# Power_Drive.net
KiCad netlist of a schematic drawn in Altium Designer
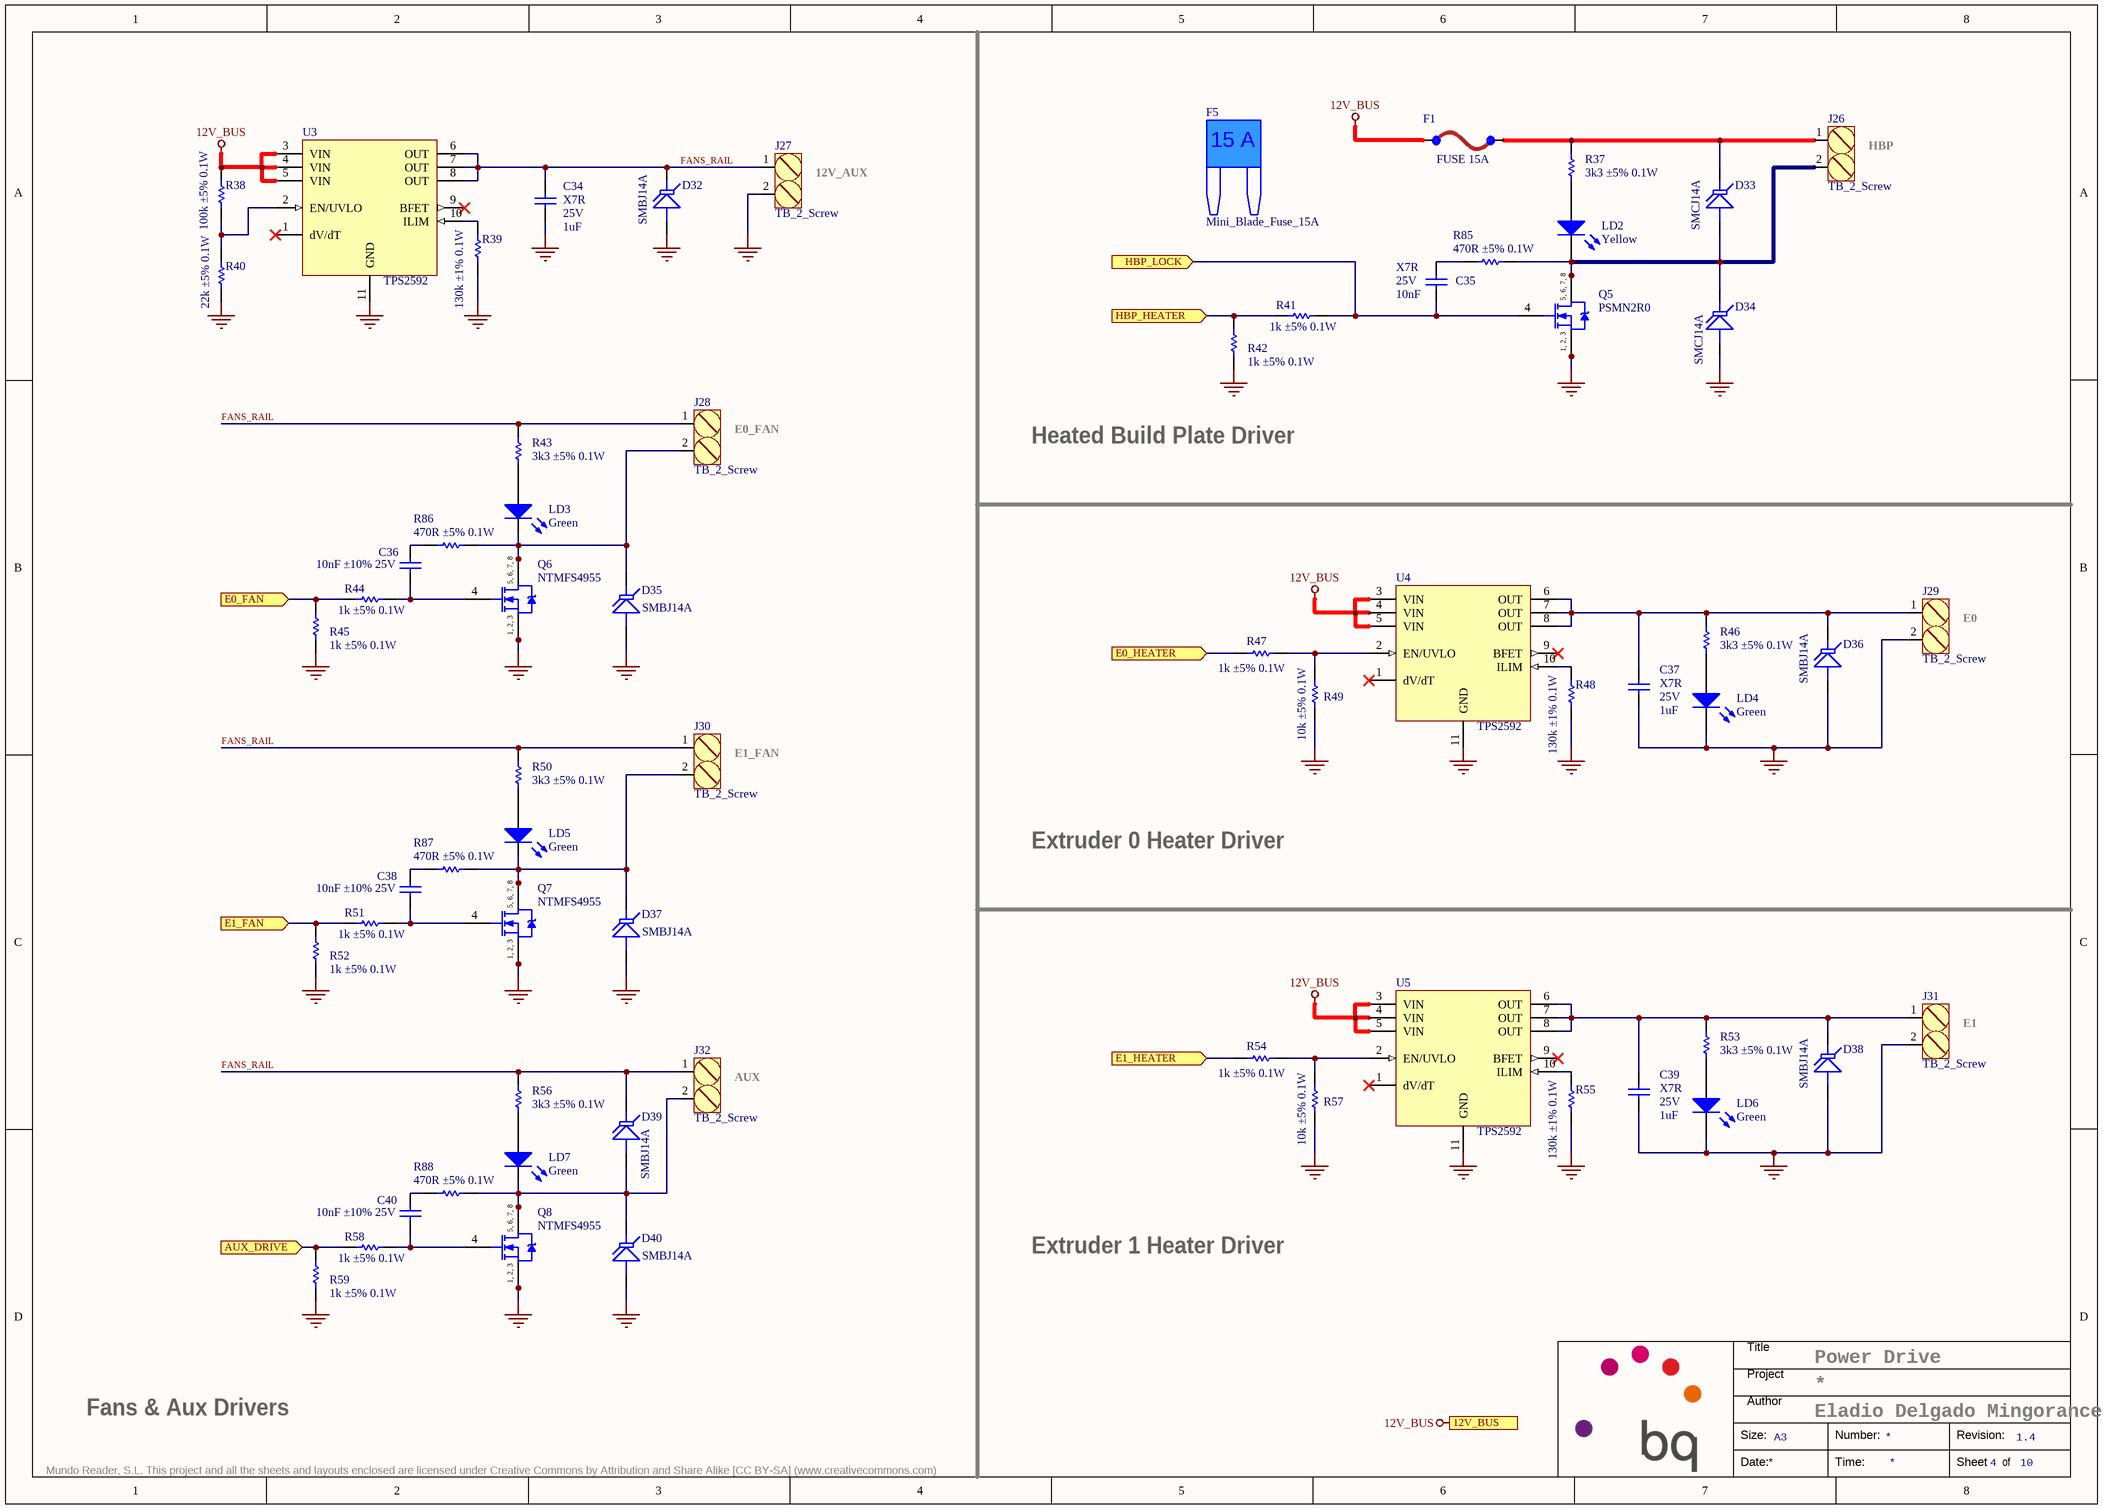
[diagram p0: Power_Drive.SchDoc]

(export (version "E")
  (design (tool "Eeschema 10.0.6"))
  (components
    (comp (ref "C34")
      (value "Capacitor")
      (footprint "C0805")
      (fields
        (field (name "DIELECTRIC") "X7R")
        (field (name "VOLTAGE") "25V")
        (field (name "CAPACITANCE") "1uF")
        (field (name "PART NUMBER") "C0805_1uF_25V_X7R")
        (field (name "TOLERANCE") "±10%")
        (field (name "MANUFACTURER") "TDK")
      )
      (libsource (lib "Pasives_Capacitor_SMD") (part "Capacitor"))
    )
    (comp (ref "C35")
      (value "Capacitor")
      (footprint "C0603")
      (fields
        (field (name "DIELECTRIC") "X7R")
        (field (name "VOLTAGE") "25V")
        (field (name "CAPACITANCE") "10nF")
        (field (name "PART NUMBER") "C0603_10nF_25V_±10%")
        (field (name "TOLERANCE") "±10%")
        (field (name "MANUFACTURER") "Kemet")
      )
      (libsource (lib "Pasives_Capacitor_SMD") (part "Capacitor"))
    )
    (comp (ref "C36")
      (value "10nF ±10% 25V")
      (footprint "C0603")
      (description "Capacitor")
      (fields (field (name "VOLTAGE") "25V") (field (name "PART NUMBER") "C0603_10nF_25V_±10%"))
      (libsource (lib "Pasives_Capacitor_SMD") (part "Capacitor"))
    )
    (comp (ref "C37")
      (value "Capacitor")
      (footprint "C0805")
      (fields
        (field (name "DIELECTRIC") "X7R")
        (field (name "VOLTAGE") "25V")
        (field (name "CAPACITANCE") "1uF")
        (field (name "PART NUMBER") "C0805_1uF_25V_X7R")
        (field (name "TOLERANCE") "±10%")
        (field (name "MANUFACTURER") "TDK")
      )
      (libsource (lib "Pasives_Capacitor_SMD") (part "Capacitor"))
    )
    (comp (ref "C38")
      (value "10nF ±10% 25V")
      (footprint "C0603")
      (description "Capacitor")
      (fields (field (name "VOLTAGE") "25V") (field (name "PART NUMBER") "C0603_10nF_25V_±10%"))
      (libsource (lib "Pasives_Capacitor_SMD") (part "Capacitor"))
    )
    (comp (ref "C39")
      (value "Capacitor")
      (footprint "C0805")
      (fields
        (field (name "DIELECTRIC") "X7R")
        (field (name "VOLTAGE") "25V")
        (field (name "CAPACITANCE") "1uF")
        (field (name "PART NUMBER") "C0805_1uF_25V_X7R")
        (field (name "TOLERANCE") "±10%")
        (field (name "MANUFACTURER") "TDK")
      )
      (libsource (lib "Pasives_Capacitor_SMD") (part "Capacitor"))
    )
    (comp (ref "C40")
      (value "Capacitor")
      (footprint "C0603")
      (fields
        (field (name "VOLTAGE") "25V")
        (field (name "PART NUMBER") "C0603_10nF_25V_±10%")
        (field (name "TOLERANCE") "±10%")
        (field (name "VARIANTS") "10nF ±10% 25V")
      )
      (libsource (lib "Pasives_Capacitor_SMD") (part "Capacitor"))
    )
    (comp (ref "D32")
      (value "SMBJ14A")
      (footprint "DO-214AA")
      (description "Transient Suppression Diodes")
      (fields (field (name "PART NUMBER") "TVS 14V SMB") (field (name "VOLTAGE") "14V"))
      (libsource (lib "Protection") (part "Zener_TVS"))
    )
    (comp (ref "D33")
      (value "SMCJ14A")
      (footprint "DO-214AB-SMC")
      (description "Transient Suppression Diodes")
      (fields (field (name "PART NUMBER") "TVS 14V SMC") (field (name "VOLTAGE") "14V"))
      (libsource (lib "Protection") (part "Zener_TVS"))
    )
    (comp (ref "D34")
      (value "SMCJ14A")
      (footprint "DO-214AB-SMC")
      (description "Transient Suppression Diodes")
      (fields (field (name "PART NUMBER") "TVS 14V SMC") (field (name "VOLTAGE") "14V"))
      (libsource (lib "Protection") (part "Zener_TVS"))
    )
    (comp (ref "D35")
      (value "SMBJ14A")
      (footprint "DO-214AA")
      (description "Transient Suppression Diodes")
      (fields (field (name "PART NUMBER") "TVS 14V SMB") (field (name "VOLTAGE") "14V"))
      (libsource (lib "Protection") (part "Zener_TVS"))
    )
    (comp (ref "D36")
      (value "SMBJ14A")
      (footprint "DO-214AA")
      (description "Transient Suppression Diodes")
      (fields (field (name "PART NUMBER") "TVS 14V SMB") (field (name "VOLTAGE") "14V"))
      (libsource (lib "Protection") (part "Zener_TVS"))
    )
    (comp (ref "D37")
      (value "SMBJ14A")
      (footprint "DO-214AA")
      (description "Transient Suppression Diodes")
      (fields (field (name "PART NUMBER") "TVS 14V SMB") (field (name "VOLTAGE") "14V"))
      (libsource (lib "Protection") (part "Zener_TVS"))
    )
    (comp (ref "D38")
      (value "SMBJ14A")
      (footprint "DO-214AA")
      (description "Transient Suppression Diodes")
      (fields (field (name "PART NUMBER") "TVS 14V SMB") (field (name "VOLTAGE") "14V"))
      (libsource (lib "Protection") (part "Zener_TVS"))
    )
    (comp (ref "D39")
      (value "SMBJ14A")
      (footprint "DO-214AA")
      (description "Transient Suppression Diodes")
      (fields (field (name "PART NUMBER") "TVS 14V SMB") (field (name "VOLTAGE") "14V"))
      (libsource (lib "Protection") (part "Zener_TVS"))
    )
    (comp (ref "D40")
      (value "SMBJ14A")
      (footprint "DO-214AA")
      (description "Transient Suppression Diodes")
      (fields (field (name "PART NUMBER") "TVS 14V SMB") (field (name "VOLTAGE") "14V"))
      (libsource (lib "Protection") (part "Zener_TVS"))
    )
    (comp (ref "F1")
      (value "FUSE 15A")
      (footprint "Fuse_Holder_TH_3568")
      (description "Thermal fuse")
      (fields (field (name "PART NUMBER") "Mini Fuse Holder Vert TH") (field (name "VOLTAGE") "500VAC"))
      (libsource (lib "Protection") (part "Thermal_Fuse"))
    )
    (comp (ref "F5")
      (value "Mini_Blade_Fuse_15A")
      (description "Protection, Mini Blade Fuse 15A")
      (fields (field (name "PART NUMBER") "Mini Blade Fuse 15A") (field (name "VOLTAGE") "32"))
      (libsource (lib "Protection") (part "Mini_Blade_Fuse_15A"))
    )
    (comp (ref "J26")
      (value "TB_2_Screw")
      (footprint "TB_5.00_2_Screw_15A")
      (description "Terminal Block Fixed with Screw")
      (fields
        (field (name "PART NUMBER") "TB_5.00_2_Screw_15A")
        (field (name "MANUFACTURER") "TE Connectivity")
      )
      (libsource (lib "Connectors_TB") (part "TB_2_Screw"))
    )
    (comp (ref "J27")
      (value "TB_2_Screw")
      (footprint "TB_5.00_2_Screw_15A")
      (description "Terminal Block Fixed with Screw")
      (fields
        (field (name "PART NUMBER") "TB_5.00_2_Screw_15A")
        (field (name "MANUFACTURER") "TE Connectivity")
      )
      (libsource (lib "Connectors_TB") (part "TB_2_Screw"))
    )
    (comp (ref "J28")
      (value "TB_2_Screw")
      (footprint "TB_5.00_2_Screw_15A")
      (description "Terminal Block Fixed with Screw")
      (fields
        (field (name "PART NUMBER") "TB_5.00_2_Screw_15A")
        (field (name "MANUFACTURER") "TE Connectivity")
      )
      (libsource (lib "Connectors_TB") (part "TB_2_Screw"))
    )
    (comp (ref "J29")
      (value "TB_2_Screw")
      (footprint "TB_5.00_2_Screw_15A")
      (description "Terminal Block Fixed with Screw")
      (fields
        (field (name "PART NUMBER") "TB_5.00_2_Screw_15A")
        (field (name "MANUFACTURER") "TE Connectivity")
      )
      (libsource (lib "Connectors_TB") (part "TB_2_Screw"))
    )
    (comp (ref "J30")
      (value "TB_2_Screw")
      (footprint "TB_5.00_2_Screw_15A")
      (description "Terminal Block Fixed with Screw")
      (fields
        (field (name "PART NUMBER") "TB_5.00_2_Screw_15A")
        (field (name "MANUFACTURER") "TE Connectivity")
      )
      (libsource (lib "Connectors_TB") (part "TB_2_Screw"))
    )
    (comp (ref "J31")
      (value "TB_2_Screw")
      (footprint "TB_5.00_2_Screw_15A")
      (description "Terminal Block Fixed with Screw")
      (fields
        (field (name "PART NUMBER") "TB_5.00_2_Screw_15A")
        (field (name "MANUFACTURER") "TE Connectivity")
      )
      (libsource (lib "Connectors_TB") (part "TB_2_Screw"))
    )
    (comp (ref "J32")
      (value "TB_2_Screw")
      (footprint "TB_5.00_2_Screw_15A")
      (description "Terminal Block Fixed with Screw")
      (fields
        (field (name "PART NUMBER") "TB_5.00_2_Screw_15A")
        (field (name "MANUFACTURER") "TE Connectivity")
      )
      (libsource (lib "Connectors_TB") (part "TB_2_Screw"))
    )
    (comp (ref "LD2")
      (value "Yellow")
      (footprint "LED0603")
      (description "Light Emitting Diode")
      (fields (field (name "PART NUMBER") "HSMY-C190") (field (name "MANUFACTURER") "Avago Technologies"))
      (libsource (lib "Optoelectronics") (part "LED"))
    )
    (comp (ref "LD3")
      (value "Green")
      (footprint "LED0603")
      (description "Light Emitting Diode")
      (fields (field (name "PART NUMBER") "HSMG-C190") (field (name "MANUFACTURER") "Avago Technologies"))
      (libsource (lib "Optoelectronics") (part "LED"))
    )
    (comp (ref "LD4")
      (value "Green")
      (footprint "LED0603")
      (description "Light Emitting Diode")
      (fields (field (name "PART NUMBER") "HSMG-C190") (field (name "MANUFACTURER") "Avago Technologies"))
      (libsource (lib "Optoelectronics") (part "LED"))
    )
    (comp (ref "LD5")
      (value "Green")
      (footprint "LED0603")
      (description "Light Emitting Diode")
      (fields (field (name "PART NUMBER") "HSMG-C190") (field (name "MANUFACTURER") "Avago Technologies"))
      (libsource (lib "Optoelectronics") (part "LED"))
    )
    (comp (ref "LD6")
      (value "Green")
      (footprint "LED0603")
      (description "Light Emitting Diode")
      (fields (field (name "PART NUMBER") "HSMG-C190") (field (name "MANUFACTURER") "Avago Technologies"))
      (libsource (lib "Optoelectronics") (part "LED"))
    )
    (comp (ref "LD7")
      (value "Green")
      (footprint "LED0603")
      (description "Light Emitting Diode")
      (fields (field (name "PART NUMBER") "HSMG-C190") (field (name "MANUFACTURER") "Avago Technologies"))
      (libsource (lib "Optoelectronics") (part "LED"))
    )
    (comp (ref "Q5")
      (value "PSMN2R0")
      (footprint "NXP_LFPAK56")
      (description "Power SO8 N-MOSFET")
      (fields (field (name "MANUFACTURER") "NXP"))
      (libsource (lib "Semiconductors_Transistors") (part "N-MOSFET Power SO8"))
    )
    (comp (ref "Q6")
      (value "NTMFS4955")
      (footprint "OS_DFN5")
      (description "Power SO8 N-MOSFET")
      (fields (field (name "MANUFACTURER") "On Semiconductor"))
      (libsource (lib "Semiconductors_Transistors") (part "N-MOSFET Power SO8"))
    )
    (comp (ref "Q7")
      (value "NTMFS4955")
      (footprint "OS_DFN5")
      (description "Power SO8 N-MOSFET")
      (fields (field (name "MANUFACTURER") "On Semiconductor"))
      (libsource (lib "Semiconductors_Transistors") (part "N-MOSFET Power SO8"))
    )
    (comp (ref "Q8")
      (value "NTMFS4955")
      (footprint "OS_DFN5")
      (description "Power SO8 N-MOSFET")
      (fields (field (name "MANUFACTURER") "On Semiconductor"))
      (libsource (lib "Semiconductors_Transistors") (part "N-MOSFET Power SO8"))
    )
    (comp (ref "R37")
      (value "3k3 ±5% 0.1W")
      (footprint "R0603")
      (description "Resistor")
      (fields (field (name "TOLERANCE") "±5%") (field (name "POWER") "0.1W"))
      (libsource (lib "Pasives_Resistor_SMD") (part "Resistor"))
    )
    (comp (ref "R38")
      (value "100k ±5% 0.1W")
      (footprint "R0603")
      (description "Resistor")
      (fields (field (name "TOLERANCE") "±5%") (field (name "POWER") "0.1W"))
      (libsource (lib "Pasives_Resistor_SMD") (part "Resistor"))
    )
    (comp (ref "R39")
      (value "130k ±1% 0.1W")
      (footprint "R0603")
      (description "Resistor")
      (fields (field (name "TOLERANCE") "±1%") (field (name "POWER") "0.1W"))
      (libsource (lib "Pasives_Resistor_SMD") (part "Resistor"))
    )
    (comp (ref "R40")
      (value "22k ±5% 0.1W")
      (footprint "R0603")
      (description "Resistor")
      (fields (field (name "TOLERANCE") "±5%") (field (name "POWER") "0.1W"))
      (libsource (lib "Pasives_Resistor_SMD") (part "Resistor"))
    )
    (comp (ref "R41")
      (value "1k ±5% 0.1W")
      (footprint "R0603")
      (description "Resistor")
      (fields (field (name "TOLERANCE") "±5%") (field (name "POWER") "0.1W"))
      (libsource (lib "Pasives_Resistor_SMD") (part "Resistor"))
    )
    (comp (ref "R42")
      (value "1k ±5% 0.1W")
      (footprint "R0603")
      (description "Resistor")
      (fields (field (name "TOLERANCE") "±5%") (field (name "POWER") "0.1W"))
      (libsource (lib "Pasives_Resistor_SMD") (part "Resistor"))
    )
    (comp (ref "R43")
      (value "3k3 ±5% 0.1W")
      (footprint "R0603")
      (description "Resistor")
      (fields (field (name "TOLERANCE") "±5%") (field (name "POWER") "0.1W"))
      (libsource (lib "Pasives_Resistor_SMD") (part "Resistor"))
    )
    (comp (ref "R44")
      (value "1k ±5% 0.1W")
      (footprint "R0603")
      (description "Resistor")
      (fields (field (name "TOLERANCE") "±5%") (field (name "POWER") "0.1W"))
      (libsource (lib "Pasives_Resistor_SMD") (part "Resistor"))
    )
    (comp (ref "R45")
      (value "1k ±5% 0.1W")
      (footprint "R0603")
      (description "Resistor")
      (fields (field (name "TOLERANCE") "±5%") (field (name "POWER") "0.1W"))
      (libsource (lib "Pasives_Resistor_SMD") (part "Resistor"))
    )
    (comp (ref "R46")
      (value "3k3 ±5% 0.1W")
      (footprint "R0603")
      (description "Resistor")
      (fields (field (name "TOLERANCE") "±5%") (field (name "POWER") "0.1W"))
      (libsource (lib "Pasives_Resistor_SMD") (part "Resistor"))
    )
    (comp (ref "R47")
      (value "1k ±5% 0.1W")
      (footprint "R0603")
      (description "Resistor")
      (fields (field (name "TOLERANCE") "±5%") (field (name "POWER") "0.1W"))
      (libsource (lib "Pasives_Resistor_SMD") (part "Resistor"))
    )
    (comp (ref "R48")
      (value "130k ±1% 0.1W")
      (footprint "R0603")
      (description "Resistor")
      (fields (field (name "TOLERANCE") "±1%") (field (name "POWER") "0.1W"))
      (libsource (lib "Pasives_Resistor_SMD") (part "Resistor"))
    )
    (comp (ref "R49")
      (value "10k ±5% 0.1W")
      (footprint "R0603")
      (description "Resistor")
      (fields (field (name "TOLERANCE") "±5%") (field (name "POWER") "0.1W"))
      (libsource (lib "Pasives_Resistor_SMD") (part "Resistor"))
    )
    (comp (ref "R50")
      (value "3k3 ±5% 0.1W")
      (footprint "R0603")
      (description "Resistor")
      (fields (field (name "TOLERANCE") "±5%") (field (name "POWER") "0.1W"))
      (libsource (lib "Pasives_Resistor_SMD") (part "Resistor"))
    )
    (comp (ref "R51")
      (value "1k ±5% 0.1W")
      (footprint "R0603")
      (description "Resistor")
      (fields (field (name "TOLERANCE") "±5%") (field (name "POWER") "0.1W"))
      (libsource (lib "Pasives_Resistor_SMD") (part "Resistor"))
    )
    (comp (ref "R52")
      (value "1k ±5% 0.1W")
      (footprint "R0603")
      (description "Resistor")
      (fields (field (name "TOLERANCE") "±5%") (field (name "POWER") "0.1W"))
      (libsource (lib "Pasives_Resistor_SMD") (part "Resistor"))
    )
    (comp (ref "R53")
      (value "3k3 ±5% 0.1W")
      (footprint "R0603")
      (description "Resistor")
      (fields (field (name "TOLERANCE") "±5%") (field (name "POWER") "0.1W"))
      (libsource (lib "Pasives_Resistor_SMD") (part "Resistor"))
    )
    (comp (ref "R54")
      (value "1k ±5% 0.1W")
      (footprint "R0603")
      (description "Resistor")
      (fields (field (name "TOLERANCE") "±5%") (field (name "POWER") "0.1W"))
      (libsource (lib "Pasives_Resistor_SMD") (part "Resistor"))
    )
    (comp (ref "R55")
      (value "130k ±1% 0.1W")
      (footprint "R0603")
      (description "Resistor")
      (fields (field (name "TOLERANCE") "±1%") (field (name "POWER") "0.1W"))
      (libsource (lib "Pasives_Resistor_SMD") (part "Resistor"))
    )
    (comp (ref "R56")
      (value "3k3 ±5% 0.1W")
      (footprint "R0603")
      (description "Resistor")
      (fields (field (name "TOLERANCE") "±5%") (field (name "POWER") "0.1W"))
      (libsource (lib "Pasives_Resistor_SMD") (part "Resistor"))
    )
    (comp (ref "R57")
      (value "10k ±5% 0.1W")
      (footprint "R0603")
      (description "Resistor")
      (fields (field (name "TOLERANCE") "±5%") (field (name "POWER") "0.1W"))
      (libsource (lib "Pasives_Resistor_SMD") (part "Resistor"))
    )
    (comp (ref "R58")
      (value "1k ±5% 0.1W")
      (footprint "R0603")
      (description "Resistor")
      (fields (field (name "TOLERANCE") "±5%") (field (name "POWER") "0.1W"))
      (libsource (lib "Pasives_Resistor_SMD") (part "Resistor"))
    )
    (comp (ref "R59")
      (value "1k ±5% 0.1W")
      (footprint "R0603")
      (description "Resistor")
      (fields (field (name "TOLERANCE") "±5%") (field (name "POWER") "0.1W"))
      (libsource (lib "Pasives_Resistor_SMD") (part "Resistor"))
    )
    (comp (ref "R85")
      (value "470R ±5% 0.1W")
      (footprint "R0603")
      (description "Resistor")
      (fields (field (name "TOLERANCE") "±5%") (field (name "POWER") "0.1W"))
      (libsource (lib "Pasives_Resistor_SMD") (part "Resistor"))
    )
    (comp (ref "R86")
      (value "470R ±5% 0.1W")
      (footprint "R0603")
      (description "Resistor")
      (fields (field (name "TOLERANCE") "±5%") (field (name "POWER") "0.1W"))
      (libsource (lib "Pasives_Resistor_SMD") (part "Resistor"))
    )
    (comp (ref "R87")
      (value "470R ±5% 0.1W")
      (footprint "R0603")
      (description "Resistor")
      (fields (field (name "TOLERANCE") "±5%") (field (name "POWER") "0.1W"))
      (libsource (lib "Pasives_Resistor_SMD") (part "Resistor"))
    )
    (comp (ref "R88")
      (value "470R ±5% 0.1W")
      (footprint "R0603")
      (description "Resistor")
      (fields (field (name "TOLERANCE") "±5%") (field (name "POWER") "0.1W"))
      (libsource (lib "Pasives_Resistor_SMD") (part "Resistor"))
    )
    (comp (ref "U3")
      (value "TPS2592")
      (footprint "S-PVSON-N10")
      (description "12V eFuse, 28 mR, 2 to 5A")
      (fields (field (name "MANUFACTURER") "Texas Instruments"))
      (libsource (lib "Power_Management") (part "TPS2592"))
    )
    (comp (ref "U4")
      (value "TPS2592")
      (footprint "S-PVSON-N10")
      (description "12V eFuse, 28 mR, 2 to 5A")
      (fields (field (name "MANUFACTURER") "Texas Instruments"))
      (libsource (lib "Power_Management") (part "TPS2592"))
    )
    (comp (ref "U5")
      (value "TPS2592")
      (footprint "S-PVSON-N10")
      (description "12V eFuse, 28 mR, 2 to 5A")
      (fields (field (name "MANUFACTURER") "Texas Instruments"))
      (libsource (lib "Power_Management") (part "TPS2592"))
    )
  )
  (nets
    (net (code "1") (name "/AUX_DRIVE") (class "Default")
      (node (ref "R58") (pin "1") (pinfunction "1_1") (pintype "passive"))
      (node (ref "R59") (pin "2") (pinfunction "2_2") (pintype "passive"))
    )
    (net (code "2") (name "/E0_FAN") (class "Default")
      (node (ref "R44") (pin "1") (pinfunction "1_1") (pintype "passive"))
      (node (ref "R45") (pin "2") (pinfunction "2_2") (pintype "passive"))
    )
    (net (code "3") (name "/E0_HEATER") (class "Default")
      (node (ref "R47") (pin "1") (pinfunction "1_1") (pintype "passive"))
    )
    (net (code "4") (name "/E1_FAN") (class "Default")
      (node (ref "R51") (pin "1") (pinfunction "1_1") (pintype "passive"))
      (node (ref "R52") (pin "2") (pinfunction "2_2") (pintype "passive"))
    )
    (net (code "5") (name "/E1_HEATER") (class "Default")
      (node (ref "R54") (pin "1") (pinfunction "1_1") (pintype "passive"))
    )
    (net (code "6") (name "/FANS_RAIL") (class "Default")
      (node (ref "C34") (pin "2") (pinfunction "2_2") (pintype "passive"))
      (node (ref "D32") (pin "K") (pinfunction "K_K") (pintype "passive"))
      (node (ref "D39") (pin "K") (pinfunction "K_K") (pintype "passive"))
      (node (ref "J27") (pin "1") (pinfunction "1_1") (pintype "passive"))
      (node (ref "J28") (pin "1") (pinfunction "1_1") (pintype "passive"))
      (node (ref "J30") (pin "1") (pinfunction "1_1") (pintype "passive"))
      (node (ref "J32") (pin "1") (pinfunction "1_1") (pintype "passive"))
      (node (ref "R43") (pin "2") (pinfunction "2_2") (pintype "passive"))
      (node (ref "R50") (pin "2") (pinfunction "2_2") (pintype "passive"))
      (node (ref "R56") (pin "2") (pinfunction "2_2") (pintype "passive"))
      (node (ref "U3") (pin "6") (pinfunction "OUT_6") (pintype "power_in"))
      (node (ref "U3") (pin "7") (pinfunction "OUT_7") (pintype "power_in"))
      (node (ref "U3") (pin "8") (pinfunction "OUT_8") (pintype "power_in"))
    )
    (net (code "7") (name "/HBP_HEATER") (class "Default")
      (node (ref "R41") (pin "1") (pinfunction "1_1") (pintype "passive"))
      (node (ref "R42") (pin "2") (pinfunction "2_2") (pintype "passive"))
    )
    (net (code "8") (name "/HBP_LOCK") (class "Default")
      (node (ref "C35") (pin "1") (pinfunction "1_1") (pintype "passive"))
      (node (ref "Q5") (pin "4") (pinfunction "G_4") (pintype "passive"))
      (node (ref "R41") (pin "2") (pinfunction "2_2") (pintype "passive"))
    )
    (net (code "9") (name "12V_BUS") (class "Default")
      (node (ref "F1") (pin "1") (pinfunction "1_1") (pintype "passive"))
      (node (ref "R38") (pin "1") (pinfunction "1_1") (pintype "passive"))
      (node (ref "U3") (pin "3") (pinfunction "VIN_3") (pintype "power_in"))
      (node (ref "U3") (pin "4") (pinfunction "VIN_4") (pintype "power_in"))
      (node (ref "U3") (pin "5") (pinfunction "VIN_5") (pintype "power_in"))
      (node (ref "U4") (pin "3") (pinfunction "VIN_3") (pintype "power_in"))
      (node (ref "U4") (pin "4") (pinfunction "VIN_4") (pintype "power_in"))
      (node (ref "U4") (pin "5") (pinfunction "VIN_5") (pintype "power_in"))
      (node (ref "U5") (pin "3") (pinfunction "VIN_3") (pintype "power_in"))
      (node (ref "U5") (pin "4") (pinfunction "VIN_4") (pintype "power_in"))
      (node (ref "U5") (pin "5") (pinfunction "VIN_5") (pintype "power_in"))
    )
    (net (code "10") (name "GND") (class "Default")
      (node (ref "C34") (pin "1") (pinfunction "1_1") (pintype "passive"))
      (node (ref "C37") (pin "1") (pinfunction "1_1") (pintype "passive"))
      (node (ref "C39") (pin "1") (pinfunction "1_1") (pintype "passive"))
      (node (ref "D32") (pin "A") (pinfunction "A_A") (pintype "passive"))
      (node (ref "D34") (pin "A") (pinfunction "A_A") (pintype "passive"))
      (node (ref "D35") (pin "A") (pinfunction "A_A") (pintype "passive"))
      (node (ref "D36") (pin "A") (pinfunction "A_A") (pintype "passive"))
      (node (ref "D37") (pin "A") (pinfunction "A_A") (pintype "passive"))
      (node (ref "D38") (pin "A") (pinfunction "A_A") (pintype "passive"))
      (node (ref "D40") (pin "A") (pinfunction "A_A") (pintype "passive"))
      (node (ref "J27") (pin "2") (pinfunction "2_2") (pintype "passive"))
      (node (ref "J29") (pin "2") (pinfunction "2_2") (pintype "passive"))
      (node (ref "J31") (pin "2") (pinfunction "2_2") (pintype "passive"))
      (node (ref "LD4") (pin "K") (pinfunction "K_K") (pintype "passive"))
      (node (ref "LD6") (pin "K") (pinfunction "K_K") (pintype "passive"))
      (node (ref "Q5") (pin "1") (pinfunction "S_1") (pintype "passive"))
      (node (ref "Q5") (pin "2") (pinfunction "S_2") (pintype "passive"))
      (node (ref "Q5") (pin "3") (pinfunction "S_3") (pintype "passive"))
      (node (ref "Q6") (pin "1") (pinfunction "S_1") (pintype "passive"))
      (node (ref "Q6") (pin "2") (pinfunction "S_2") (pintype "passive"))
      (node (ref "Q6") (pin "3") (pinfunction "S_3") (pintype "passive"))
      (node (ref "Q7") (pin "1") (pinfunction "S_1") (pintype "passive"))
      (node (ref "Q7") (pin "2") (pinfunction "S_2") (pintype "passive"))
      (node (ref "Q7") (pin "3") (pinfunction "S_3") (pintype "passive"))
      (node (ref "Q8") (pin "1") (pinfunction "S_1") (pintype "passive"))
      (node (ref "Q8") (pin "2") (pinfunction "S_2") (pintype "passive"))
      (node (ref "Q8") (pin "3") (pinfunction "S_3") (pintype "passive"))
      (node (ref "R39") (pin "1") (pinfunction "1_1") (pintype "passive"))
      (node (ref "R40") (pin "1") (pinfunction "1_1") (pintype "passive"))
      (node (ref "R42") (pin "1") (pinfunction "1_1") (pintype "passive"))
      (node (ref "R45") (pin "1") (pinfunction "1_1") (pintype "passive"))
      (node (ref "R48") (pin "1") (pinfunction "1_1") (pintype "passive"))
      (node (ref "R49") (pin "1") (pinfunction "1_1") (pintype "passive"))
      (node (ref "R52") (pin "1") (pinfunction "1_1") (pintype "passive"))
      (node (ref "R55") (pin "1") (pinfunction "1_1") (pintype "passive"))
      (node (ref "R57") (pin "1") (pinfunction "1_1") (pintype "passive"))
      (node (ref "R59") (pin "1") (pinfunction "1_1") (pintype "passive"))
      (node (ref "U3") (pin "11") (pinfunction "GND_11") (pintype "power_in"))
      (node (ref "U4") (pin "11") (pinfunction "GND_11") (pintype "power_in"))
      (node (ref "U5") (pin "11") (pinfunction "GND_11") (pintype "power_in"))
    )
    (net (code "11") (name "Net-(C35-Pad2)") (class "Default")
      (node (ref "C35") (pin "2") (pinfunction "2_2") (pintype "passive"))
      (node (ref "R85") (pin "1") (pinfunction "1_1") (pintype "passive"))
    )
    (net (code "12") (name "Net-(C36-Pad2)") (class "Default")
      (node (ref "C36") (pin "2") (pinfunction "2_2") (pintype "passive"))
      (node (ref "R86") (pin "1") (pinfunction "1_1") (pintype "passive"))
    )
    (net (code "13") (name "Net-(C37-Pad2)") (class "Default")
      (node (ref "C37") (pin "2") (pinfunction "2_2") (pintype "passive"))
      (node (ref "D36") (pin "K") (pinfunction "K_K") (pintype "passive"))
      (node (ref "J29") (pin "1") (pinfunction "1_1") (pintype "passive"))
      (node (ref "R46") (pin "2") (pinfunction "2_2") (pintype "passive"))
      (node (ref "U4") (pin "6") (pinfunction "OUT_6") (pintype "power_in"))
      (node (ref "U4") (pin "7") (pinfunction "OUT_7") (pintype "power_in"))
      (node (ref "U4") (pin "8") (pinfunction "OUT_8") (pintype "power_in"))
    )
    (net (code "14") (name "Net-(C38-Pad2)") (class "Default")
      (node (ref "C38") (pin "2") (pinfunction "2_2") (pintype "passive"))
      (node (ref "R87") (pin "1") (pinfunction "1_1") (pintype "passive"))
    )
    (net (code "15") (name "Net-(C39-Pad2)") (class "Default")
      (node (ref "C39") (pin "2") (pinfunction "2_2") (pintype "passive"))
      (node (ref "D38") (pin "K") (pinfunction "K_K") (pintype "passive"))
      (node (ref "J31") (pin "1") (pinfunction "1_1") (pintype "passive"))
      (node (ref "R53") (pin "2") (pinfunction "2_2") (pintype "passive"))
      (node (ref "U5") (pin "6") (pinfunction "OUT_6") (pintype "power_in"))
      (node (ref "U5") (pin "7") (pinfunction "OUT_7") (pintype "power_in"))
      (node (ref "U5") (pin "8") (pinfunction "OUT_8") (pintype "power_in"))
    )
    (net (code "16") (name "Net-(C40-Pad2)") (class "Default")
      (node (ref "C40") (pin "2") (pinfunction "2_2") (pintype "passive"))
      (node (ref "R88") (pin "1") (pinfunction "1_1") (pintype "passive"))
    )
    (net (code "17") (name "Net-(D33-PadA)") (class "Default")
      (node (ref "D33") (pin "A") (pinfunction "A_A") (pintype "passive"))
      (node (ref "D34") (pin "K") (pinfunction "K_K") (pintype "passive"))
      (node (ref "J26") (pin "2") (pinfunction "2_2") (pintype "passive"))
      (node (ref "LD2") (pin "K") (pinfunction "K_K") (pintype "passive"))
      (node (ref "Q5") (pin "5") (pinfunction "D_5") (pintype "passive"))
      (node (ref "Q5") (pin "6") (pinfunction "D_6") (pintype "passive"))
      (node (ref "Q5") (pin "7") (pinfunction "D_7") (pintype "passive"))
      (node (ref "Q5") (pin "8") (pinfunction "D_8") (pintype "passive"))
      (node (ref "R85") (pin "2") (pinfunction "2_2") (pintype "passive"))
    )
    (net (code "18") (name "Net-(D33-PadK)") (class "Default")
      (node (ref "D33") (pin "K") (pinfunction "K_K") (pintype "passive"))
      (node (ref "F1") (pin "2") (pinfunction "2_2") (pintype "passive"))
      (node (ref "J26") (pin "1") (pinfunction "1_1") (pintype "passive"))
      (node (ref "R37") (pin "2") (pinfunction "2_2") (pintype "passive"))
    )
    (net (code "19") (name "Net-(D35-PadK)") (class "Default")
      (node (ref "D35") (pin "K") (pinfunction "K_K") (pintype "passive"))
      (node (ref "J28") (pin "2") (pinfunction "2_2") (pintype "passive"))
      (node (ref "LD3") (pin "K") (pinfunction "K_K") (pintype "passive"))
      (node (ref "Q6") (pin "5") (pinfunction "D_5") (pintype "passive"))
      (node (ref "Q6") (pin "6") (pinfunction "D_6") (pintype "passive"))
      (node (ref "Q6") (pin "7") (pinfunction "D_7") (pintype "passive"))
      (node (ref "Q6") (pin "8") (pinfunction "D_8") (pintype "passive"))
      (node (ref "R86") (pin "2") (pinfunction "2_2") (pintype "passive"))
    )
    (net (code "20") (name "Net-(D37-PadK)") (class "Default")
      (node (ref "D37") (pin "K") (pinfunction "K_K") (pintype "passive"))
      (node (ref "J30") (pin "2") (pinfunction "2_2") (pintype "passive"))
      (node (ref "LD5") (pin "K") (pinfunction "K_K") (pintype "passive"))
      (node (ref "Q7") (pin "5") (pinfunction "D_5") (pintype "passive"))
      (node (ref "Q7") (pin "6") (pinfunction "D_6") (pintype "passive"))
      (node (ref "Q7") (pin "7") (pinfunction "D_7") (pintype "passive"))
      (node (ref "Q7") (pin "8") (pinfunction "D_8") (pintype "passive"))
      (node (ref "R87") (pin "2") (pinfunction "2_2") (pintype "passive"))
    )
    (net (code "21") (name "Net-(D39-PadA)") (class "Default")
      (node (ref "D39") (pin "A") (pinfunction "A_A") (pintype "passive"))
      (node (ref "D40") (pin "K") (pinfunction "K_K") (pintype "passive"))
      (node (ref "J32") (pin "2") (pinfunction "2_2") (pintype "passive"))
      (node (ref "LD7") (pin "K") (pinfunction "K_K") (pintype "passive"))
      (node (ref "Q8") (pin "5") (pinfunction "D_5") (pintype "passive"))
      (node (ref "Q8") (pin "6") (pinfunction "D_6") (pintype "passive"))
      (node (ref "Q8") (pin "7") (pinfunction "D_7") (pintype "passive"))
      (node (ref "Q8") (pin "8") (pinfunction "D_8") (pintype "passive"))
      (node (ref "R88") (pin "2") (pinfunction "2_2") (pintype "passive"))
    )
    (net (code "22") (name "Net-(LD2-PadA)") (class "Default")
      (node (ref "LD2") (pin "A") (pinfunction "A_A") (pintype "passive"))
      (node (ref "R37") (pin "1") (pinfunction "1_1") (pintype "passive"))
    )
    (net (code "23") (name "Net-(LD3-PadA)") (class "Default")
      (node (ref "LD3") (pin "A") (pinfunction "A_A") (pintype "passive"))
      (node (ref "R43") (pin "1") (pinfunction "1_1") (pintype "passive"))
    )
    (net (code "24") (name "Net-(LD4-PadA)") (class "Default")
      (node (ref "LD4") (pin "A") (pinfunction "A_A") (pintype "passive"))
      (node (ref "R46") (pin "1") (pinfunction "1_1") (pintype "passive"))
    )
    (net (code "25") (name "Net-(LD5-PadA)") (class "Default")
      (node (ref "LD5") (pin "A") (pinfunction "A_A") (pintype "passive"))
      (node (ref "R50") (pin "1") (pinfunction "1_1") (pintype "passive"))
    )
    (net (code "26") (name "Net-(LD6-PadA)") (class "Default")
      (node (ref "LD6") (pin "A") (pinfunction "A_A") (pintype "passive"))
      (node (ref "R53") (pin "1") (pinfunction "1_1") (pintype "passive"))
    )
    (net (code "27") (name "Net-(LD7-PadA)") (class "Default")
      (node (ref "LD7") (pin "A") (pinfunction "A_A") (pintype "passive"))
      (node (ref "R56") (pin "1") (pinfunction "1_1") (pintype "passive"))
    )
    (net (code "28") (name "Net-(Q6-G)") (class "Default")
      (node (ref "C36") (pin "1") (pinfunction "1_1") (pintype "passive"))
      (node (ref "Q6") (pin "4") (pinfunction "G_4") (pintype "passive"))
      (node (ref "R44") (pin "2") (pinfunction "2_2") (pintype "passive"))
    )
    (net (code "29") (name "Net-(Q7-G)") (class "Default")
      (node (ref "C38") (pin "1") (pinfunction "1_1") (pintype "passive"))
      (node (ref "Q7") (pin "4") (pinfunction "G_4") (pintype "passive"))
      (node (ref "R51") (pin "2") (pinfunction "2_2") (pintype "passive"))
    )
    (net (code "30") (name "Net-(Q8-G)") (class "Default")
      (node (ref "C40") (pin "1") (pinfunction "1_1") (pintype "passive"))
      (node (ref "Q8") (pin "4") (pinfunction "G_4") (pintype "passive"))
      (node (ref "R58") (pin "2") (pinfunction "2_2") (pintype "passive"))
    )
    (net (code "31") (name "Net-(U3-EN{slash}UVLO)") (class "Default")
      (node (ref "R38") (pin "2") (pinfunction "2_2") (pintype "passive"))
      (node (ref "R40") (pin "2") (pinfunction "2_2") (pintype "passive"))
      (node (ref "U3") (pin "2") (pinfunction "EN/UVLO_2") (pintype "input"))
    )
    (net (code "32") (name "Net-(U3-ILIM)") (class "Default")
      (node (ref "R39") (pin "2") (pinfunction "2_2") (pintype "passive"))
      (node (ref "U3") (pin "10") (pinfunction "ILIM_10") (pintype "input"))
    )
    (net (code "33") (name "Net-(U4-EN{slash}UVLO)") (class "Default")
      (node (ref "R47") (pin "2") (pinfunction "2_2") (pintype "passive"))
      (node (ref "R49") (pin "2") (pinfunction "2_2") (pintype "passive"))
      (node (ref "U4") (pin "2") (pinfunction "EN/UVLO_2") (pintype "input"))
    )
    (net (code "34") (name "Net-(U4-ILIM)") (class "Default")
      (node (ref "R48") (pin "2") (pinfunction "2_2") (pintype "passive"))
      (node (ref "U4") (pin "10") (pinfunction "ILIM_10") (pintype "input"))
    )
    (net (code "35") (name "Net-(U5-EN{slash}UVLO)") (class "Default")
      (node (ref "R54") (pin "2") (pinfunction "2_2") (pintype "passive"))
      (node (ref "R57") (pin "2") (pinfunction "2_2") (pintype "passive"))
      (node (ref "U5") (pin "2") (pinfunction "EN/UVLO_2") (pintype "input"))
    )
    (net (code "36") (name "Net-(U5-ILIM)") (class "Default")
      (node (ref "R55") (pin "2") (pinfunction "2_2") (pintype "passive"))
      (node (ref "U5") (pin "10") (pinfunction "ILIM_10") (pintype "input"))
    )
    (net (code "37") (name "unconnected-(U3-BFET-Pad9)") (class "Default")
      (node (ref "U3") (pin "9") (pinfunction "BFET_9") (pintype "output+no_connect"))
    )
    (net (code "38") (name "unconnected-(U3-dV{slash}dT-Pad1)") (class "Default")
      (node (ref "U3") (pin "1") (pinfunction "dV/dT_1") (pintype "passive+no_connect"))
    )
    (net (code "39") (name "unconnected-(U4-BFET-Pad9)") (class "Default")
      (node (ref "U4") (pin "9") (pinfunction "BFET_9") (pintype "output+no_connect"))
    )
    (net (code "40") (name "unconnected-(U4-dV{slash}dT-Pad1)") (class "Default")
      (node (ref "U4") (pin "1") (pinfunction "dV/dT_1") (pintype "passive+no_connect"))
    )
    (net (code "41") (name "unconnected-(U5-BFET-Pad9)") (class "Default")
      (node (ref "U5") (pin "9") (pinfunction "BFET_9") (pintype "output+no_connect"))
    )
    (net (code "42") (name "unconnected-(U5-dV{slash}dT-Pad1)") (class "Default")
      (node (ref "U5") (pin "1") (pinfunction "dV/dT_1") (pintype "passive+no_connect"))
    )
  )
)
